# MegaShield-thruhole.net
KiCad netlist of a schematic drawn in EAGLE
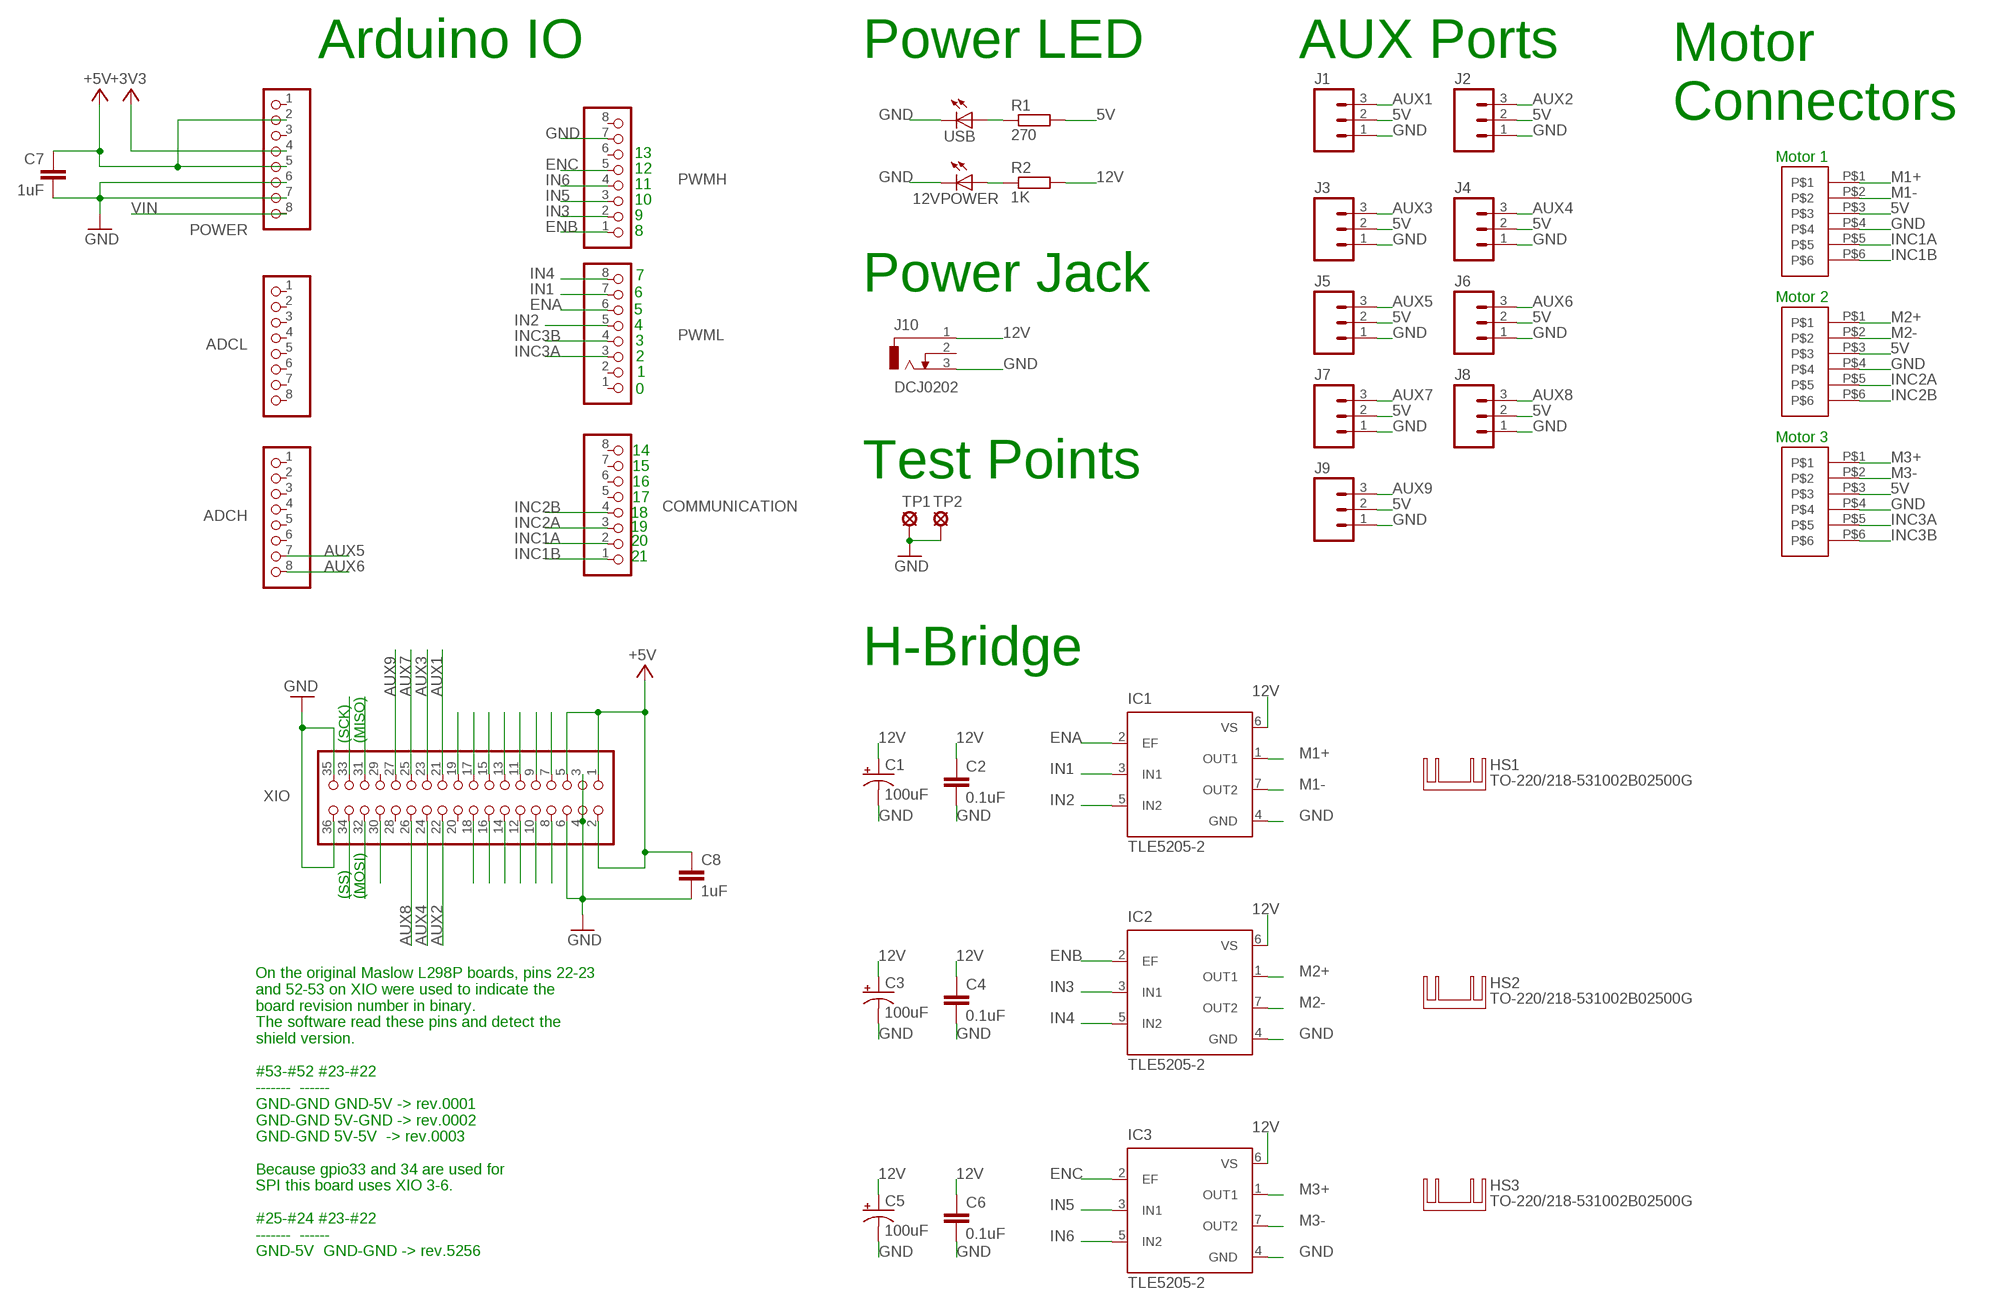
[diagram p0: schematic, sheet 1]

(export (version "E")
  (design (tool "Eeschema 10.0.6"))
  (components
    (comp (ref "12VPOWER")
      (value "LED_ELD260")
      (footprint "eagle-import:LED_LD260")
      (libsource (lib "eagle-import") (part "LED_ELD260"))
    )
    (comp (ref "ADCH")
      (value "8x1F-H8.5")
      (footprint "eagle-import:1X08")
      (libsource (lib "eagle-import") (part "PINHD-1X8"))
    )
    (comp (ref "ADCL")
      (value "PINHD-1X8")
      (footprint "eagle-import:1X08")
      (libsource (lib "eagle-import") (part "pinhead_PINHD-1X8"))
    )
    (comp (ref "C1")
      (value "100uF")
      (footprint "eagle-import:CPOL-RADIAL-100UF-25V")
      (libsource (lib "eagle-import") (part "CAP_POLPTH1"))
    )
    (comp (ref "C2")
      (value "0.1uF")
      (footprint "eagle-import:CAP-PTH-SMALL")
      (libsource (lib "eagle-import") (part "CAPPTH"))
    )
    (comp (ref "C3")
      (value "100uF")
      (footprint "eagle-import:CPOL-RADIAL-100UF-25V")
      (libsource (lib "eagle-import") (part "CAP_POLPTH1"))
    )
    (comp (ref "C4")
      (value "0.1uF")
      (footprint "eagle-import:CAP-PTH-SMALL")
      (libsource (lib "eagle-import") (part "CAPPTH"))
    )
    (comp (ref "C5")
      (value "100uF")
      (footprint "eagle-import:CPOL-RADIAL-100UF-25V")
      (libsource (lib "eagle-import") (part "CAP_POLPTH1"))
    )
    (comp (ref "C6")
      (value "0.1uF")
      (footprint "eagle-import:CAP-PTH-SMALL")
      (libsource (lib "eagle-import") (part "CAPPTH"))
    )
    (comp (ref "C7")
      (value "1uF")
      (footprint "eagle-import:CAP-PTH-SMALL")
      (libsource (lib "eagle-import") (part "CAPPTH"))
    )
    (comp (ref "C8")
      (value "1uF")
      (footprint "eagle-import:CAP-PTH-SMALL")
      (libsource (lib "eagle-import") (part "CAPPTH"))
    )
    (comp (ref "COMMUNICATION")
      (value "PINHD-1X8")
      (footprint "eagle-import:1X08")
      (libsource (lib "eagle-import") (part "pinhead_PINHD-1X8"))
    )
    (comp (ref "HS1")
      (value "TO-220/218-531002B02500G")
      (footprint "eagle-import:531XXXXXXXX")
      (libsource (lib "eagle-import") (part "TO-220/218-531XXXXXXXX"))
    )
    (comp (ref "HS2")
      (value "TO-220/218-531002B02500G")
      (footprint "eagle-import:531XXXXXXXX")
      (libsource (lib "eagle-import") (part "TO-220/218-531XXXXXXXX"))
    )
    (comp (ref "HS3")
      (value "TO-220/218-531002B02500G")
      (footprint "eagle-import:531XXXXXXXX")
      (libsource (lib "eagle-import") (part "TO-220/218-531XXXXXXXX"))
    )
    (comp (ref "IC1")
      (value "TLE5205-2")
      (footprint "eagle-import:P-TO220-7-11")
      (libsource (lib "eagle-import") (part "TLE5205-2"))
    )
    (comp (ref "IC2")
      (value "TLE5205-2")
      (footprint "eagle-import:P-TO220-7-11")
      (libsource (lib "eagle-import") (part "TLE5205-2"))
    )
    (comp (ref "IC3")
      (value "TLE5205-2")
      (footprint "eagle-import:P-TO220-7-11")
      (libsource (lib "eagle-import") (part "TLE5205-2"))
    )
    (comp (ref "J1")
      (value "M03LOCK")
      (footprint "eagle-import:1X03_LOCK")
      (libsource (lib "eagle-import") (part "M03LOCK"))
    )
    (comp (ref "J2")
      (value "M03LOCK")
      (footprint "eagle-import:1X03_LOCK")
      (libsource (lib "eagle-import") (part "M03LOCK"))
    )
    (comp (ref "J3")
      (value "M03LOCK")
      (footprint "eagle-import:1X03_LOCK")
      (libsource (lib "eagle-import") (part "M03LOCK"))
    )
    (comp (ref "J4")
      (value "M03LOCK")
      (footprint "eagle-import:1X03_LOCK")
      (libsource (lib "eagle-import") (part "M03LOCK"))
    )
    (comp (ref "J5")
      (value "M03LOCK")
      (footprint "eagle-import:1X03_LOCK")
      (libsource (lib "eagle-import") (part "M03LOCK"))
    )
    (comp (ref "J6")
      (value "M03LOCK")
      (footprint "eagle-import:1X03_LOCK")
      (libsource (lib "eagle-import") (part "M03LOCK"))
    )
    (comp (ref "J7")
      (value "M03LOCK")
      (footprint "eagle-import:1X03_LOCK")
      (libsource (lib "eagle-import") (part "M03LOCK"))
    )
    (comp (ref "J8")
      (value "M03LOCK")
      (footprint "eagle-import:1X03_LOCK")
      (libsource (lib "eagle-import") (part "M03LOCK"))
    )
    (comp (ref "J9")
      (value "M03LOCK")
      (footprint "eagle-import:1X03_LOCK")
      (libsource (lib "eagle-import") (part "M03LOCK"))
    )
    (comp (ref "J10")
      (value "DCJ0202")
      (footprint "eagle-import:DCJ0202")
      (libsource (lib "eagle-import") (part "DCJ0202"))
    )
    (comp (ref "MP1")
      (value "JST-PH-6")
      (footprint "eagle-import:JST-PHR-6-SMD")
      (libsource (lib "eagle-import") (part "JST-PH-6"))
    )
    (comp (ref "MP2")
      (value "JST-PH-6")
      (footprint "eagle-import:JST-PHR-6-SMD")
      (libsource (lib "eagle-import") (part "JST-PH-6"))
    )
    (comp (ref "MP3")
      (value "JST-PH-6")
      (footprint "eagle-import:JST-PHR-6-SMD")
      (libsource (lib "eagle-import") (part "JST-PH-6"))
    )
    (comp (ref "POWER")
      (value "8x1F-H8.5")
      (footprint "eagle-import:1X08")
      (libsource (lib "eagle-import") (part "PINHD-1X8"))
    )
    (comp (ref "PWMH")
      (value "PINHD-1X8")
      (footprint "eagle-import:1X08")
      (libsource (lib "eagle-import") (part "pinhead_PINHD-1X8"))
    )
    (comp (ref "PWML")
      (value "PINHD-1X8")
      (footprint "eagle-import:1X08")
      (libsource (lib "eagle-import") (part "pinhead_PINHD-1X8"))
    )
    (comp (ref "R1")
      (value "270")
      (footprint "eagle-import:0207_10")
      (libsource (lib "eagle-import") (part "R0207/10"))
    )
    (comp (ref "R2")
      (value "1K")
      (footprint "eagle-import:0207_10")
      (libsource (lib "eagle-import") (part "R0207/10"))
    )
    (comp (ref "TP1")
      (value "LSP10")
      (footprint "eagle-import:LSP10")
      (libsource (lib "eagle-import") (part "LSP10"))
    )
    (comp (ref "TP2")
      (value "LSP10")
      (footprint "eagle-import:LSP10")
      (libsource (lib "eagle-import") (part "LSP10"))
    )
    (comp (ref "USB")
      (value "LED_ELD260")
      (footprint "eagle-import:LED_LD260")
      (libsource (lib "eagle-import") (part "LED_ELD260"))
    )
    (comp (ref "XIO")
      (value "18x2F-H8.5")
      (footprint "eagle-import:2X18")
      (libsource (lib "eagle-import") (part "PINHD-2X18"))
    )
  )
  (nets
    (net (code "1") (name "+3V3") (class "Default")
      (node (ref "POWER") (pin "4") (pinfunction "4_4") (pintype "passive"))
    )
    (net (code "2") (name "+5V") (class "Default")
      (node (ref "C7") (pin "1") (pinfunction "1_1") (pintype "passive"))
      (node (ref "C8") (pin "1") (pinfunction "1_1") (pintype "passive"))
      (node (ref "J1") (pin "2") (pinfunction "2_2") (pintype "passive"))
      (node (ref "J2") (pin "2") (pinfunction "2_2") (pintype "passive"))
      (node (ref "J3") (pin "2") (pinfunction "2_2") (pintype "passive"))
      (node (ref "J4") (pin "2") (pinfunction "2_2") (pintype "passive"))
      (node (ref "J5") (pin "2") (pinfunction "2_2") (pintype "passive"))
      (node (ref "J6") (pin "2") (pinfunction "2_2") (pintype "passive"))
      (node (ref "J7") (pin "2") (pinfunction "2_2") (pintype "passive"))
      (node (ref "J8") (pin "2") (pinfunction "2_2") (pintype "passive"))
      (node (ref "J9") (pin "2") (pinfunction "2_2") (pintype "passive"))
      (node (ref "MP1") (pin "P$3") (pinfunction "P$3_P$3") (pintype "bidirectional"))
      (node (ref "MP2") (pin "P$3") (pinfunction "P$3_P$3") (pintype "bidirectional"))
      (node (ref "MP3") (pin "P$3") (pinfunction "P$3_P$3") (pintype "bidirectional"))
      (node (ref "POWER") (pin "2") (pinfunction "2_2") (pintype "passive"))
      (node (ref "POWER") (pin "5") (pinfunction "5_5") (pintype "passive"))
      (node (ref "R1") (pin "2") (pinfunction "2_2") (pintype "passive"))
      (node (ref "XIO") (pin "1") (pinfunction "1_1") (pintype "passive"))
      (node (ref "XIO") (pin "2") (pinfunction "2_2") (pintype "passive"))
      (node (ref "XIO") (pin "5") (pinfunction "5_5") (pintype "passive"))
    )
    (net (code "3") (name "/12V") (class "Default")
      (node (ref "C1") (pin "1") (pinfunction "+_1") (pintype "passive"))
      (node (ref "C2") (pin "1") (pinfunction "1_1") (pintype "passive"))
      (node (ref "C3") (pin "1") (pinfunction "+_1") (pintype "passive"))
      (node (ref "C4") (pin "1") (pinfunction "1_1") (pintype "passive"))
      (node (ref "C5") (pin "1") (pinfunction "+_1") (pintype "passive"))
      (node (ref "C6") (pin "1") (pinfunction "1_1") (pintype "passive"))
      (node (ref "IC1") (pin "6") (pinfunction "VS_6") (pintype "input"))
      (node (ref "IC2") (pin "6") (pinfunction "VS_6") (pintype "input"))
      (node (ref "IC3") (pin "6") (pinfunction "VS_6") (pintype "input"))
      (node (ref "J10") (pin "1") (pinfunction "1_1") (pintype "passive"))
      (node (ref "R2") (pin "2") (pinfunction "2_2") (pintype "passive"))
    )
    (net (code "4") (name "/AUX1") (class "Default")
      (node (ref "J1") (pin "3") (pinfunction "3_3") (pintype "passive"))
      (node (ref "XIO") (pin "21") (pinfunction "21_21") (pintype "passive"))
    )
    (net (code "5") (name "/AUX2") (class "Default")
      (node (ref "J2") (pin "3") (pinfunction "3_3") (pintype "passive"))
      (node (ref "XIO") (pin "22") (pinfunction "22_22") (pintype "passive"))
    )
    (net (code "6") (name "/AUX3") (class "Default")
      (node (ref "J3") (pin "3") (pinfunction "3_3") (pintype "passive"))
      (node (ref "XIO") (pin "23") (pinfunction "23_23") (pintype "passive"))
    )
    (net (code "7") (name "/AUX4") (class "Default")
      (node (ref "J4") (pin "3") (pinfunction "3_3") (pintype "passive"))
      (node (ref "XIO") (pin "24") (pinfunction "24_24") (pintype "passive"))
    )
    (net (code "8") (name "/AUX5") (class "Default")
      (node (ref "ADCH") (pin "7") (pinfunction "7_7") (pintype "passive"))
      (node (ref "J5") (pin "3") (pinfunction "3_3") (pintype "passive"))
    )
    (net (code "9") (name "/AUX6") (class "Default")
      (node (ref "ADCH") (pin "8") (pinfunction "8_8") (pintype "passive"))
      (node (ref "J6") (pin "3") (pinfunction "3_3") (pintype "passive"))
    )
    (net (code "10") (name "/AUX7") (class "Default")
      (node (ref "J7") (pin "3") (pinfunction "3_3") (pintype "passive"))
      (node (ref "XIO") (pin "25") (pinfunction "25_25") (pintype "passive"))
    )
    (net (code "11") (name "/AUX8") (class "Default")
      (node (ref "J8") (pin "3") (pinfunction "3_3") (pintype "passive"))
      (node (ref "XIO") (pin "26") (pinfunction "26_26") (pintype "passive"))
    )
    (net (code "12") (name "/AUX9") (class "Default")
      (node (ref "J9") (pin "3") (pinfunction "3_3") (pintype "passive"))
      (node (ref "XIO") (pin "27") (pinfunction "27_27") (pintype "passive"))
    )
    (net (code "13") (name "/ENA") (class "Default")
      (node (ref "IC1") (pin "2") (pinfunction "EF_2") (pintype "open_collector"))
      (node (ref "PWML") (pin "6") (pinfunction "6_6") (pintype "passive"))
    )
    (net (code "14") (name "/ENB") (class "Default")
      (node (ref "IC2") (pin "2") (pinfunction "EF_2") (pintype "open_collector"))
      (node (ref "PWMH") (pin "1") (pinfunction "1_1") (pintype "passive"))
    )
    (net (code "15") (name "/ENC") (class "Default")
      (node (ref "IC3") (pin "2") (pinfunction "EF_2") (pintype "open_collector"))
      (node (ref "PWMH") (pin "5") (pinfunction "5_5") (pintype "passive"))
    )
    (net (code "16") (name "/IN1") (class "Default")
      (node (ref "IC1") (pin "3") (pinfunction "IN1_3") (pintype "input"))
      (node (ref "PWML") (pin "7") (pinfunction "7_7") (pintype "passive"))
    )
    (net (code "17") (name "/IN2") (class "Default")
      (node (ref "IC1") (pin "5") (pinfunction "IN2_5") (pintype "input"))
      (node (ref "PWML") (pin "5") (pinfunction "5_5") (pintype "passive"))
    )
    (net (code "18") (name "/IN3") (class "Default")
      (node (ref "IC2") (pin "3") (pinfunction "IN1_3") (pintype "input"))
      (node (ref "PWMH") (pin "2") (pinfunction "2_2") (pintype "passive"))
    )
    (net (code "19") (name "/IN4") (class "Default")
      (node (ref "IC2") (pin "5") (pinfunction "IN2_5") (pintype "input"))
      (node (ref "PWML") (pin "8") (pinfunction "8_8") (pintype "passive"))
    )
    (net (code "20") (name "/IN5") (class "Default")
      (node (ref "IC3") (pin "3") (pinfunction "IN1_3") (pintype "input"))
      (node (ref "PWMH") (pin "3") (pinfunction "3_3") (pintype "passive"))
    )
    (net (code "21") (name "/IN6") (class "Default")
      (node (ref "IC3") (pin "5") (pinfunction "IN2_5") (pintype "input"))
      (node (ref "PWMH") (pin "4") (pinfunction "4_4") (pintype "passive"))
    )
    (net (code "22") (name "/INC1A") (class "Default")
      (node (ref "COMMUNICATION") (pin "2") (pinfunction "2_2") (pintype "passive"))
      (node (ref "MP1") (pin "P$5") (pinfunction "P$5_P$5") (pintype "bidirectional"))
    )
    (net (code "23") (name "/INC1B") (class "Default")
      (node (ref "COMMUNICATION") (pin "1") (pinfunction "1_1") (pintype "passive"))
      (node (ref "MP1") (pin "P$6") (pinfunction "P$6_P$6") (pintype "bidirectional"))
    )
    (net (code "24") (name "/INC2A") (class "Default")
      (node (ref "COMMUNICATION") (pin "3") (pinfunction "3_3") (pintype "passive"))
      (node (ref "MP2") (pin "P$5") (pinfunction "P$5_P$5") (pintype "bidirectional"))
    )
    (net (code "25") (name "/INC2B") (class "Default")
      (node (ref "COMMUNICATION") (pin "4") (pinfunction "4_4") (pintype "passive"))
      (node (ref "MP2") (pin "P$6") (pinfunction "P$6_P$6") (pintype "bidirectional"))
    )
    (net (code "26") (name "/INC3A") (class "Default")
      (node (ref "MP3") (pin "P$5") (pinfunction "P$5_P$5") (pintype "bidirectional"))
      (node (ref "PWML") (pin "3") (pinfunction "3_3") (pintype "passive"))
    )
    (net (code "27") (name "/INC3B") (class "Default")
      (node (ref "MP3") (pin "P$6") (pinfunction "P$6_P$6") (pintype "bidirectional"))
      (node (ref "PWML") (pin "4") (pinfunction "4_4") (pintype "passive"))
    )
    (net (code "28") (name "/M1+") (class "Default")
      (node (ref "IC1") (pin "1") (pinfunction "OUT1_1") (pintype "output"))
      (node (ref "MP1") (pin "P$1") (pinfunction "P$1_P$1") (pintype "bidirectional"))
    )
    (net (code "29") (name "/M1-") (class "Default")
      (node (ref "IC1") (pin "7") (pinfunction "OUT2_7") (pintype "output"))
      (node (ref "MP1") (pin "P$2") (pinfunction "P$2_P$2") (pintype "bidirectional"))
    )
    (net (code "30") (name "/M2+") (class "Default")
      (node (ref "IC2") (pin "1") (pinfunction "OUT1_1") (pintype "output"))
      (node (ref "MP2") (pin "P$1") (pinfunction "P$1_P$1") (pintype "bidirectional"))
    )
    (net (code "31") (name "/M2-") (class "Default")
      (node (ref "IC2") (pin "7") (pinfunction "OUT2_7") (pintype "output"))
      (node (ref "MP2") (pin "P$2") (pinfunction "P$2_P$2") (pintype "bidirectional"))
    )
    (net (code "32") (name "/M3+") (class "Default")
      (node (ref "IC3") (pin "1") (pinfunction "OUT1_1") (pintype "output"))
      (node (ref "MP3") (pin "P$1") (pinfunction "P$1_P$1") (pintype "bidirectional"))
    )
    (net (code "33") (name "/M3-") (class "Default")
      (node (ref "IC3") (pin "7") (pinfunction "OUT2_7") (pintype "output"))
      (node (ref "MP3") (pin "P$2") (pinfunction "P$2_P$2") (pintype "bidirectional"))
    )
    (net (code "34") (name "/VIN") (class "Default")
      (node (ref "POWER") (pin "8") (pinfunction "8_8") (pintype "passive"))
    )
    (net (code "35") (name "GND") (class "Default")
      (node (ref "12VPOWER") (pin "K") (pinfunction "C_K") (pintype "passive"))
      (node (ref "C1") (pin "2") (pinfunction "-_2") (pintype "passive"))
      (node (ref "C2") (pin "2") (pinfunction "2_2") (pintype "passive"))
      (node (ref "C3") (pin "2") (pinfunction "-_2") (pintype "passive"))
      (node (ref "C4") (pin "2") (pinfunction "2_2") (pintype "passive"))
      (node (ref "C5") (pin "2") (pinfunction "-_2") (pintype "passive"))
      (node (ref "C6") (pin "2") (pinfunction "2_2") (pintype "passive"))
      (node (ref "C7") (pin "2") (pinfunction "2_2") (pintype "passive"))
      (node (ref "C8") (pin "2") (pinfunction "2_2") (pintype "passive"))
      (node (ref "IC1") (pin "4") (pinfunction "GND_4") (pintype "power_in"))
      (node (ref "IC2") (pin "4") (pinfunction "GND_4") (pintype "power_in"))
      (node (ref "IC3") (pin "4") (pinfunction "GND_4") (pintype "power_in"))
      (node (ref "J1") (pin "1") (pinfunction "1_1") (pintype "passive"))
      (node (ref "J10") (pin "3") (pinfunction "3_3") (pintype "passive"))
      (node (ref "J2") (pin "1") (pinfunction "1_1") (pintype "passive"))
      (node (ref "J3") (pin "1") (pinfunction "1_1") (pintype "passive"))
      (node (ref "J4") (pin "1") (pinfunction "1_1") (pintype "passive"))
      (node (ref "J5") (pin "1") (pinfunction "1_1") (pintype "passive"))
      (node (ref "J6") (pin "1") (pinfunction "1_1") (pintype "passive"))
      (node (ref "J7") (pin "1") (pinfunction "1_1") (pintype "passive"))
      (node (ref "J8") (pin "1") (pinfunction "1_1") (pintype "passive"))
      (node (ref "J9") (pin "1") (pinfunction "1_1") (pintype "passive"))
      (node (ref "MP1") (pin "P$4") (pinfunction "P$4_P$4") (pintype "bidirectional"))
      (node (ref "MP2") (pin "P$4") (pinfunction "P$4_P$4") (pintype "bidirectional"))
      (node (ref "MP3") (pin "P$4") (pinfunction "P$4_P$4") (pintype "bidirectional"))
      (node (ref "POWER") (pin "6") (pinfunction "6_6") (pintype "passive"))
      (node (ref "POWER") (pin "7") (pinfunction "7_7") (pintype "passive"))
      (node (ref "PWMH") (pin "7") (pinfunction "7_7") (pintype "passive"))
      (node (ref "TP1") (pin "MP") (pinfunction "MP_MP") (pintype "passive"))
      (node (ref "TP2") (pin "MP") (pinfunction "MP_MP") (pintype "passive"))
      (node (ref "USB") (pin "K") (pinfunction "C_K") (pintype "passive"))
      (node (ref "XIO") (pin "3") (pinfunction "3_3") (pintype "passive"))
      (node (ref "XIO") (pin "35") (pinfunction "35_35") (pintype "passive"))
      (node (ref "XIO") (pin "36") (pinfunction "36_36") (pintype "passive"))
      (node (ref "XIO") (pin "4") (pinfunction "4_4") (pintype "passive"))
      (node (ref "XIO") (pin "6") (pinfunction "6_6") (pintype "passive"))
    )
    (net (code "36") (name "Net-(12VPOWER-PadA)") (class "Default")
      (node (ref "12VPOWER") (pin "A") (pinfunction "A_A") (pintype "passive"))
      (node (ref "R2") (pin "1") (pinfunction "1_1") (pintype "passive"))
    )
    (net (code "37") (name "Net-(R1-Pad1)") (class "Default")
      (node (ref "R1") (pin "1") (pinfunction "1_1") (pintype "passive"))
      (node (ref "USB") (pin "A") (pinfunction "A_A") (pintype "passive"))
    )
    (net (code "38") (name "unconnected-(ADCH-Pad1)") (class "Default")
      (node (ref "ADCH") (pin "1") (pinfunction "1_1") (pintype "passive"))
    )
    (net (code "39") (name "unconnected-(ADCH-Pad2)") (class "Default")
      (node (ref "ADCH") (pin "2") (pinfunction "2_2") (pintype "passive"))
    )
    (net (code "40") (name "unconnected-(ADCH-Pad3)") (class "Default")
      (node (ref "ADCH") (pin "3") (pinfunction "3_3") (pintype "passive"))
    )
    (net (code "41") (name "unconnected-(ADCH-Pad4)") (class "Default")
      (node (ref "ADCH") (pin "4") (pinfunction "4_4") (pintype "passive"))
    )
    (net (code "42") (name "unconnected-(ADCH-Pad5)") (class "Default")
      (node (ref "ADCH") (pin "5") (pinfunction "5_5") (pintype "passive"))
    )
    (net (code "43") (name "unconnected-(ADCH-Pad6)") (class "Default")
      (node (ref "ADCH") (pin "6") (pinfunction "6_6") (pintype "passive"))
    )
    (net (code "44") (name "unconnected-(ADCL-Pad1)") (class "Default")
      (node (ref "ADCL") (pin "1") (pinfunction "1_1") (pintype "passive"))
    )
    (net (code "45") (name "unconnected-(ADCL-Pad2)") (class "Default")
      (node (ref "ADCL") (pin "2") (pinfunction "2_2") (pintype "passive"))
    )
    (net (code "46") (name "unconnected-(ADCL-Pad3)") (class "Default")
      (node (ref "ADCL") (pin "3") (pinfunction "3_3") (pintype "passive"))
    )
    (net (code "47") (name "unconnected-(ADCL-Pad4)") (class "Default")
      (node (ref "ADCL") (pin "4") (pinfunction "4_4") (pintype "passive"))
    )
    (net (code "48") (name "unconnected-(ADCL-Pad5)") (class "Default")
      (node (ref "ADCL") (pin "5") (pinfunction "5_5") (pintype "passive"))
    )
    (net (code "49") (name "unconnected-(ADCL-Pad6)") (class "Default")
      (node (ref "ADCL") (pin "6") (pinfunction "6_6") (pintype "passive"))
    )
    (net (code "50") (name "unconnected-(ADCL-Pad7)") (class "Default")
      (node (ref "ADCL") (pin "7") (pinfunction "7_7") (pintype "passive"))
    )
    (net (code "51") (name "unconnected-(ADCL-Pad8)") (class "Default")
      (node (ref "ADCL") (pin "8") (pinfunction "8_8") (pintype "passive"))
    )
    (net (code "52") (name "unconnected-(COMMUNICATION-Pad5)") (class "Default")
      (node (ref "COMMUNICATION") (pin "5") (pinfunction "5_5") (pintype "passive"))
    )
    (net (code "53") (name "unconnected-(COMMUNICATION-Pad6)") (class "Default")
      (node (ref "COMMUNICATION") (pin "6") (pinfunction "6_6") (pintype "passive"))
    )
    (net (code "54") (name "unconnected-(COMMUNICATION-Pad7)") (class "Default")
      (node (ref "COMMUNICATION") (pin "7") (pinfunction "7_7") (pintype "passive"))
    )
    (net (code "55") (name "unconnected-(COMMUNICATION-Pad8)") (class "Default")
      (node (ref "COMMUNICATION") (pin "8") (pinfunction "8_8") (pintype "passive"))
    )
    (net (code "56") (name "unconnected-(J10-Pad2)") (class "Default")
      (node (ref "J10") (pin "2") (pinfunction "2_2") (pintype "passive"))
    )
    (net (code "57") (name "unconnected-(POWER-Pad1)") (class "Default")
      (node (ref "POWER") (pin "1") (pinfunction "1_1") (pintype "passive"))
    )
    (net (code "58") (name "unconnected-(POWER-Pad3)") (class "Default")
      (node (ref "POWER") (pin "3") (pinfunction "3_3") (pintype "passive"))
    )
    (net (code "59") (name "unconnected-(PWMH-Pad6)") (class "Default")
      (node (ref "PWMH") (pin "6") (pinfunction "6_6") (pintype "passive"))
    )
    (net (code "60") (name "unconnected-(PWMH-Pad8)") (class "Default")
      (node (ref "PWMH") (pin "8") (pinfunction "8_8") (pintype "passive"))
    )
    (net (code "61") (name "unconnected-(PWML-Pad1)") (class "Default")
      (node (ref "PWML") (pin "1") (pinfunction "1_1") (pintype "passive"))
    )
    (net (code "62") (name "unconnected-(PWML-Pad2)") (class "Default")
      (node (ref "PWML") (pin "2") (pinfunction "2_2") (pintype "passive"))
    )
    (net (code "63") (name "unconnected-(XIO-Pad7)") (class "Default")
      (node (ref "XIO") (pin "7") (pinfunction "7_7") (pintype "passive"))
    )
    (net (code "64") (name "unconnected-(XIO-Pad8)") (class "Default")
      (node (ref "XIO") (pin "8") (pinfunction "8_8") (pintype "passive"))
    )
    (net (code "65") (name "unconnected-(XIO-Pad9)") (class "Default")
      (node (ref "XIO") (pin "9") (pinfunction "9_9") (pintype "passive"))
    )
    (net (code "66") (name "unconnected-(XIO-Pad10)") (class "Default")
      (node (ref "XIO") (pin "10") (pinfunction "10_10") (pintype "passive"))
    )
    (net (code "67") (name "unconnected-(XIO-Pad11)") (class "Default")
      (node (ref "XIO") (pin "11") (pinfunction "11_11") (pintype "passive"))
    )
    (net (code "68") (name "unconnected-(XIO-Pad12)") (class "Default")
      (node (ref "XIO") (pin "12") (pinfunction "12_12") (pintype "passive"))
    )
    (net (code "69") (name "unconnected-(XIO-Pad13)") (class "Default")
      (node (ref "XIO") (pin "13") (pinfunction "13_13") (pintype "passive"))
    )
    (net (code "70") (name "unconnected-(XIO-Pad14)") (class "Default")
      (node (ref "XIO") (pin "14") (pinfunction "14_14") (pintype "passive"))
    )
    (net (code "71") (name "unconnected-(XIO-Pad15)") (class "Default")
      (node (ref "XIO") (pin "15") (pinfunction "15_15") (pintype "passive"))
    )
    (net (code "72") (name "unconnected-(XIO-Pad16)") (class "Default")
      (node (ref "XIO") (pin "16") (pinfunction "16_16") (pintype "passive"))
    )
    (net (code "73") (name "unconnected-(XIO-Pad17)") (class "Default")
      (node (ref "XIO") (pin "17") (pinfunction "17_17") (pintype "passive"))
    )
    (net (code "74") (name "unconnected-(XIO-Pad18)") (class "Default")
      (node (ref "XIO") (pin "18") (pinfunction "18_18") (pintype "passive"))
    )
    (net (code "75") (name "unconnected-(XIO-Pad19)") (class "Default")
      (node (ref "XIO") (pin "19") (pinfunction "19_19") (pintype "passive"))
    )
    (net (code "76") (name "unconnected-(XIO-Pad20)") (class "Default")
      (node (ref "XIO") (pin "20") (pinfunction "20_20") (pintype "passive"))
    )
    (net (code "77") (name "unconnected-(XIO-Pad28)") (class "Default")
      (node (ref "XIO") (pin "28") (pinfunction "28_28") (pintype "passive"))
    )
    (net (code "78") (name "unconnected-(XIO-Pad29)") (class "Default")
      (node (ref "XIO") (pin "29") (pinfunction "29_29") (pintype "passive"))
    )
    (net (code "79") (name "unconnected-(XIO-Pad30)") (class "Default")
      (node (ref "XIO") (pin "30") (pinfunction "30_30") (pintype "passive"))
    )
    (net (code "80") (name "unconnected-(XIO-Pad31)") (class "Default")
      (node (ref "XIO") (pin "31") (pinfunction "31_31") (pintype "passive"))
    )
    (net (code "81") (name "unconnected-(XIO-Pad32)") (class "Default")
      (node (ref "XIO") (pin "32") (pinfunction "32_32") (pintype "passive"))
    )
    (net (code "82") (name "unconnected-(XIO-Pad33)") (class "Default")
      (node (ref "XIO") (pin "33") (pinfunction "33_33") (pintype "passive"))
    )
    (net (code "83") (name "unconnected-(XIO-Pad34)") (class "Default")
      (node (ref "XIO") (pin "34") (pinfunction "34_34") (pintype "passive"))
    )
  )
)
